# GSB-S05-V00-CAN3.net
KiCad netlist of a schematic drawn in Altium Designer
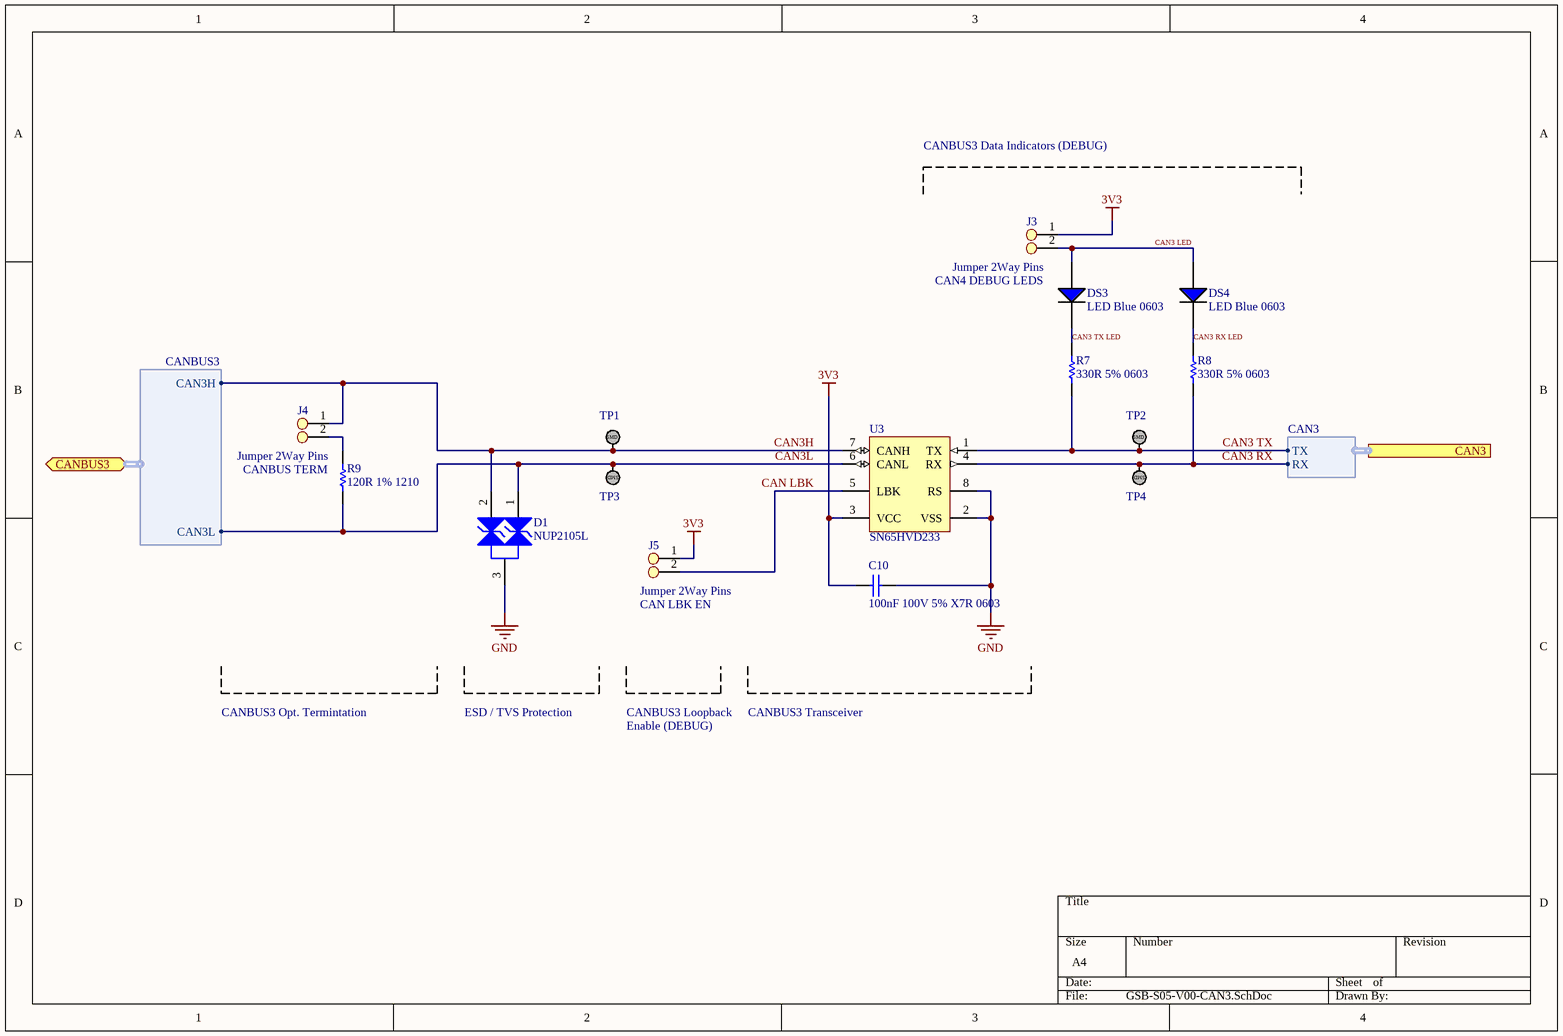
[diagram p0: GSB-S05-V00-CAN3.SchDoc]

(export (version "E")
  (design (tool "Eeschema 10.0.6"))
  (components
    (comp (ref "C10")
      (value "100nF 100V 5% X7R 0603")
      (footprint "Cap_Ceramic_0603")
      (description "Capacitor, Ceramic, SMD, 100nF, 100V, 5%, X7R, 0603")
      (libsource (lib "StandardCapacitors") (part "100nF 100V 5% X7R 0603"))
    )
    (comp (ref "D1")
      (value "NUP2105L")
      (footprint "NUP2105L")
      (libsource (lib "QUTMS_CANLibrary") (part "NUP2105L"))
    )
    (comp (ref "DS3")
      (value "LED Blue 0603")
      (footprint "LED BLUE 0603")
      (libsource (lib "QUTMS_LEDLibrary") (part "LED Blue 0603"))
    )
    (comp (ref "DS4")
      (value "LED Blue 0603")
      (footprint "LED BLUE 0603")
      (libsource (lib "QUTMS_LEDLibrary") (part "LED Blue 0603"))
    )
    (comp (ref "J3")
      (value "Jumper 2Way Pins")
      (footprint "Jumper_2Way_Pin")
      (description "Jumper 2Way Side Pins")
      (libsource (lib "QUTMS_JumperLibrary") (part "Jumper 2Way Side Pins"))
    )
    (comp (ref "J4")
      (value "Jumper 2Way Pins")
      (footprint "Jumper_2Way_Pin")
      (description "Jumper 2Way Side Pins")
      (libsource (lib "QUTMS_JumperLibrary") (part "Jumper 2Way Side Pins"))
    )
    (comp (ref "J5")
      (value "Jumper 2Way Pins")
      (footprint "Jumper_2Way_Pin")
      (description "Jumper 2Way Side Pins")
      (libsource (lib "QUTMS_JumperLibrary") (part "Jumper 2Way Side Pins"))
    )
    (comp (ref "R7")
      (value "330R 5% 0603")
      (footprint "Res_ThinFilm_0603")
      (description "Resistor, SMD, 330R, 0.1W, 5%, 0603")
      (libsource (lib "StandardResistors") (part "330R 5% 0603"))
    )
    (comp (ref "R8")
      (value "330R 5% 0603")
      (footprint "Res_ThinFilm_0603")
      (description "Resistor, SMD, 330R, 0.1W, 5%, 0603")
      (libsource (lib "StandardResistors") (part "330R 5% 0603"))
    )
    (comp (ref "R9")
      (value "120R 1% 1210")
      (footprint "Res_ThinFilm_1210")
      (description "Resistor, SMD, 120R, 0.25W, 1%, 1210")
      (libsource (lib "StandardResistors") (part "120R 1% 1210"))
    )
    (comp (ref "TP1")
      (value "TestPoint_SMD")
      (footprint "TestPointSMD")
      (libsource (lib "StandardTest") (part "TestPoint_SMD"))
    )
    (comp (ref "TP2")
      (value "TestPoint_SMD")
      (footprint "TestPointSMD")
      (libsource (lib "StandardTest") (part "TestPoint_SMD"))
    )
    (comp (ref "TP3")
      (value "TestPoint_SMD")
      (footprint "TestPointSMD")
      (libsource (lib "StandardTest") (part "TestPoint_SMD"))
    )
    (comp (ref "TP4")
      (value "TestPoint_SMD")
      (footprint "TestPointSMD")
      (libsource (lib "StandardTest") (part "TestPoint_SMD"))
    )
    (comp (ref "U3")
      (value "SN65HVD233")
      (footprint "SN65HVD233DR")
      (libsource (lib "QUTMS_CANLibrary") (part "SN65HVD233"))
    )
  )
  (nets
    (net (code "3") (name "/CAN LBK") (class "Default")
      (node (ref "J5") (pin "2") (pinfunction "2_2") (pintype "passive"))
      (node (ref "U3") (pin "5") (pinfunction "LBK_5") (pintype "passive"))
    )
    (net (code "4") (name "/CAN3 LED") (class "Default")
      (node (ref "DS3") (pin "1") (pinfunction "A_1") (pintype "passive"))
      (node (ref "DS4") (pin "1") (pinfunction "A_1") (pintype "passive"))
      (node (ref "J3") (pin "2") (pinfunction "2_2") (pintype "passive"))
    )
    (net (code "5") (name "/CAN3 RX") (class "Default")
      (node (ref "R8") (pin "1") (pinfunction "1_1") (pintype "passive"))
      (node (ref "TP4") (pin "1") (pinfunction "1_1") (pintype "passive"))
      (node (ref "U3") (pin "4") (pinfunction "RX_4") (pintype "output"))
    )
    (net (code "6") (name "/CAN3 RX LED") (class "Default")
      (node (ref "DS4") (pin "2") (pinfunction "C_2") (pintype "passive"))
      (node (ref "R8") (pin "2") (pinfunction "2_2") (pintype "passive"))
    )
    (net (code "7") (name "/CAN3 TX") (class "Default")
      (node (ref "R7") (pin "1") (pinfunction "1_1") (pintype "passive"))
      (node (ref "TP2") (pin "1") (pinfunction "1_1") (pintype "passive"))
      (node (ref "U3") (pin "1") (pinfunction "TX_1") (pintype "input"))
    )
    (net (code "8") (name "/CAN3 TX LED") (class "Default")
      (node (ref "DS3") (pin "2") (pinfunction "C_2") (pintype "passive"))
      (node (ref "R7") (pin "2") (pinfunction "2_2") (pintype "passive"))
    )
    (net (code "9") (name "/CAN3H") (class "Default")
      (node (ref "D1") (pin "2") (pinfunction "2_2") (pintype "passive"))
      (node (ref "J4") (pin "1") (pinfunction "1_1") (pintype "passive"))
      (node (ref "TP1") (pin "1") (pinfunction "1_1") (pintype "passive"))
      (node (ref "U3") (pin "7") (pinfunction "CANH_7") (pintype "bidirectional"))
    )
    (net (code "10") (name "/CAN3L") (class "Default")
      (node (ref "D1") (pin "1") (pinfunction "1_1") (pintype "passive"))
      (node (ref "R9") (pin "1") (pinfunction "1_1") (pintype "passive"))
      (node (ref "TP3") (pin "1") (pinfunction "1_1") (pintype "passive"))
      (node (ref "U3") (pin "6") (pinfunction "CANL_6") (pintype "bidirectional"))
    )
    (net (code "13") (name "3V3") (class "Default")
      (node (ref "C10") (pin "2") (pinfunction "2_2") (pintype "passive"))
      (node (ref "J3") (pin "1") (pinfunction "1_1") (pintype "passive"))
      (node (ref "J5") (pin "1") (pinfunction "1_1") (pintype "passive"))
      (node (ref "U3") (pin "3") (pinfunction "VCC_3") (pintype "passive"))
    )
    (net (code "14") (name "GND") (class "Default")
      (node (ref "C10") (pin "1") (pinfunction "1_1") (pintype "passive"))
      (node (ref "D1") (pin "3") (pinfunction "3_3") (pintype "passive"))
      (node (ref "U3") (pin "2") (pinfunction "VSS_2") (pintype "passive"))
      (node (ref "U3") (pin "8") (pinfunction "RS_8") (pintype "passive"))
    )
    (net (code "15") (name "Net-(J4-Pad2)") (class "Default")
      (node (ref "J4") (pin "2") (pinfunction "2_2") (pintype "passive"))
      (node (ref "R9") (pin "2") (pinfunction "2_2") (pintype "passive"))
    )
  )
)
